# Load_Cell_Acquisition.net
KiCad netlist of a schematic drawn in Altium Designer
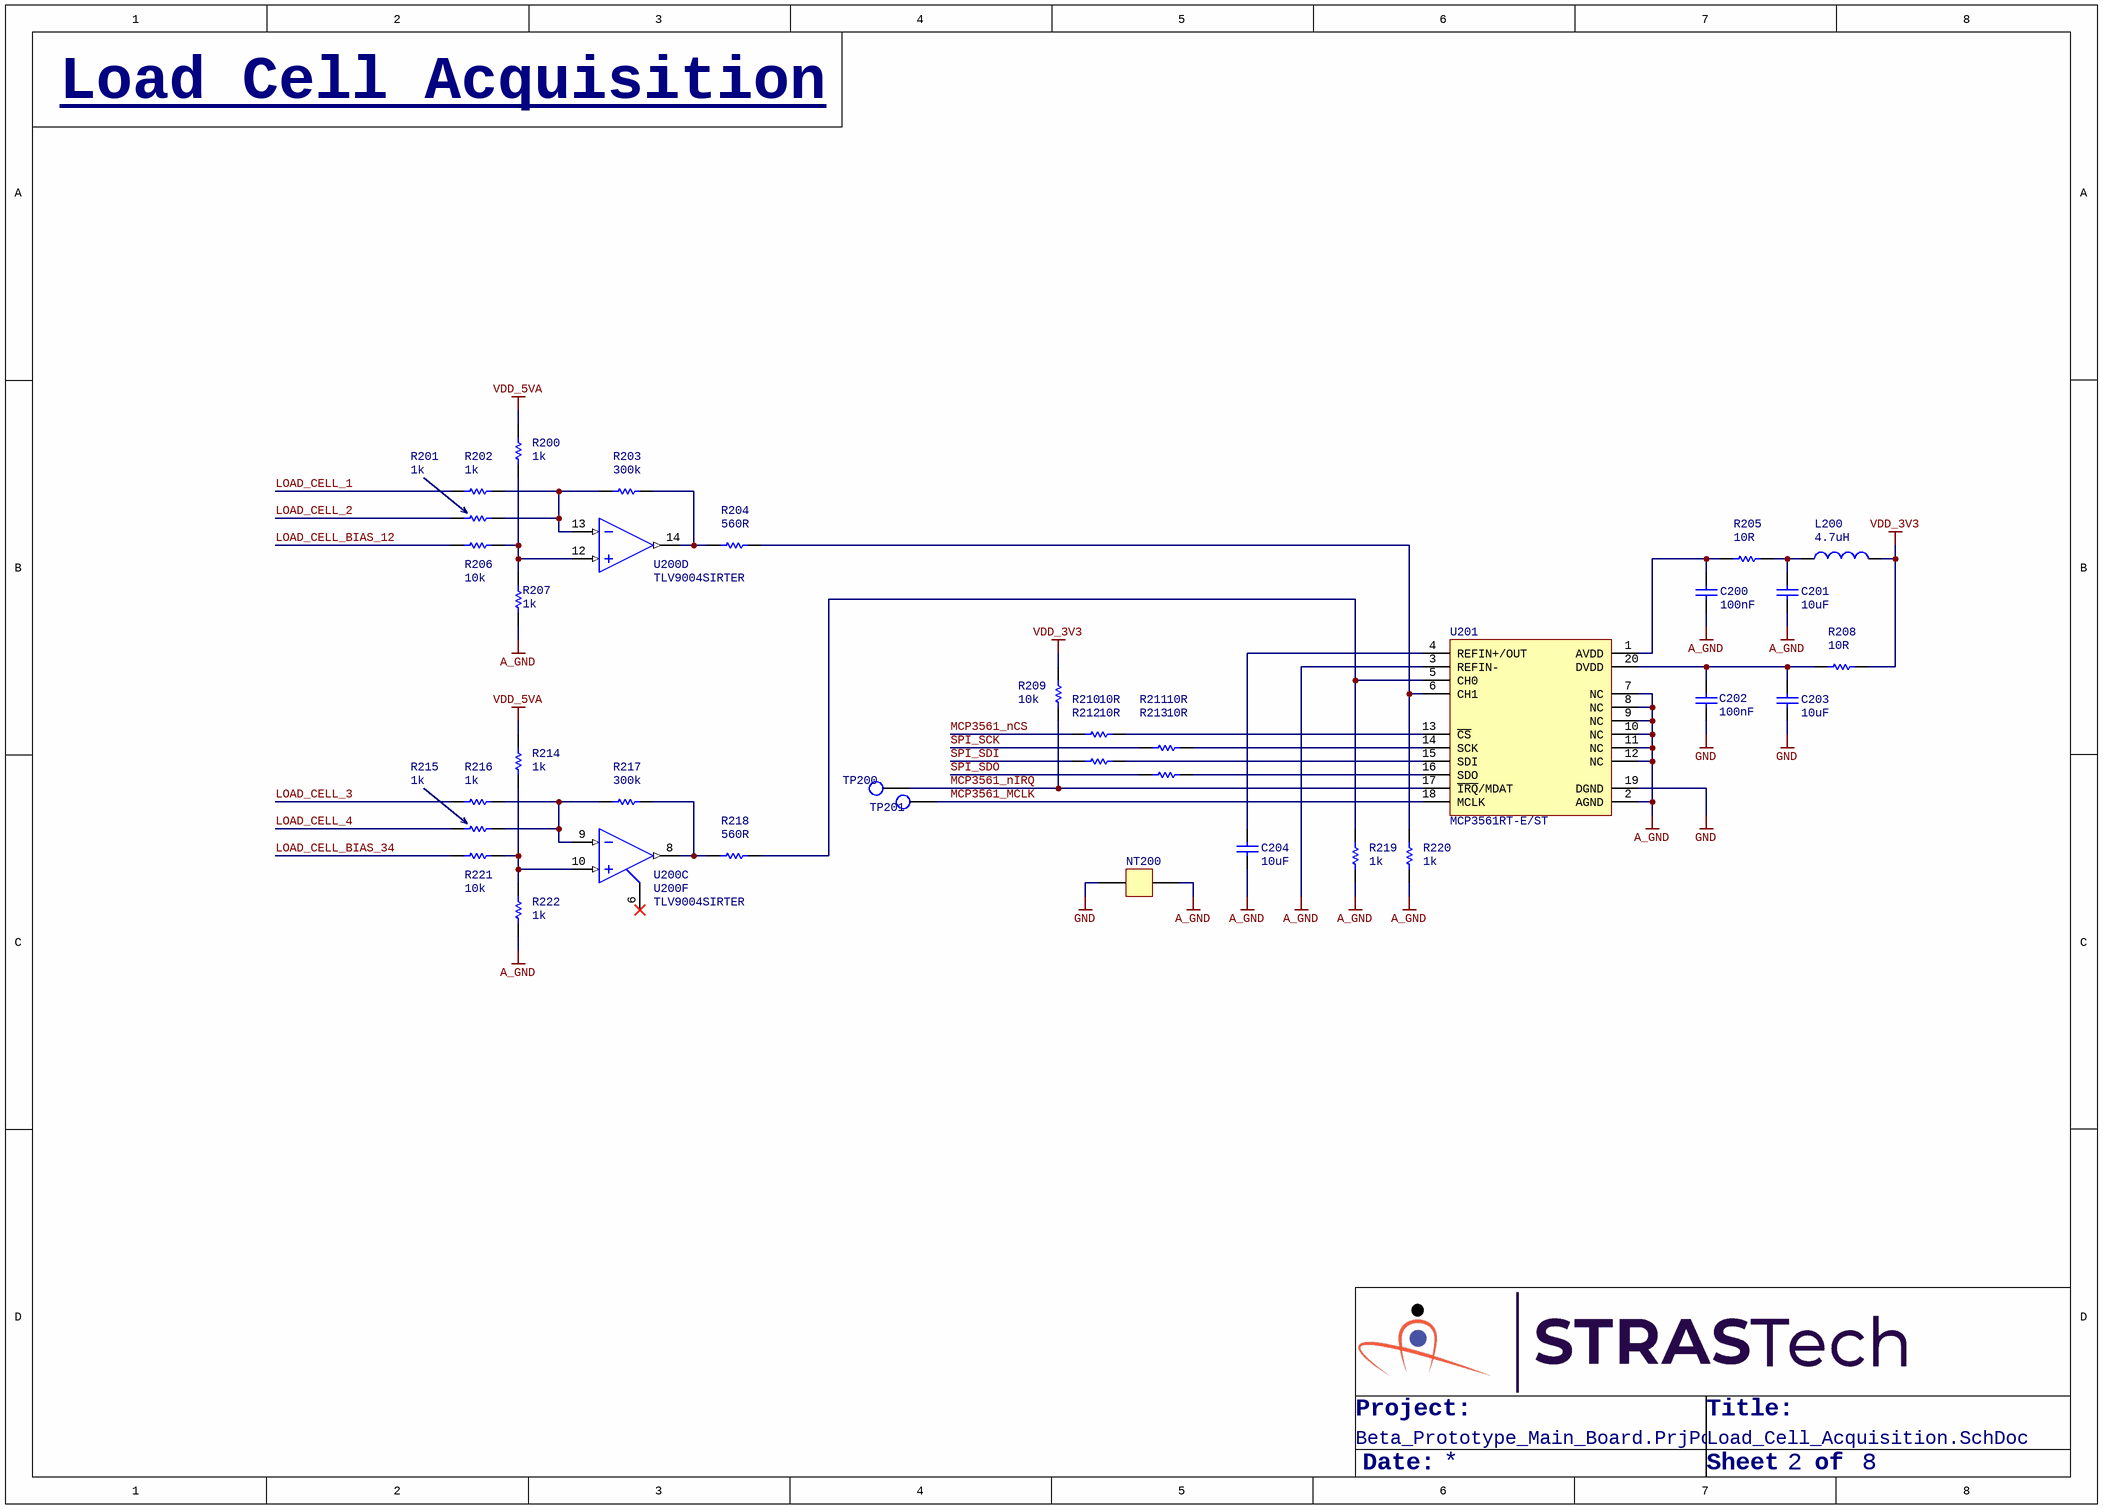
[diagram p0: Load_Cell_Acquisition.SchDoc]

(export (version "E")
  (design (tool "Eeschema 10.0.6"))
  (components
    (comp (ref "C200")
      (value "100nF")
      (footprint "Cap,SMD,0402")
      (description "0.1µF ±10% 25V Ceramic Capacitor X7R 0402 (1005 Metric)")
      (fields
        (field (name "VENDOR PART NUMBER") "490-14603-1-ND")
        (field (name "MANUFACTURER") "Murata Electronics")
        (field (name "CREATEDBY") "Judd Foster")
      )
      (libsource (lib "symbols") (part "CAP,Cer,100nF,25VDC,X7R,0402"))
    )
    (comp (ref "C201")
      (value "10uF")
      (footprint "Cap,SMD,0402")
      (description "10 µF ±20% 10V Ceramic Capacitor X5R 0402 (1005 Metric)")
      (fields
        (field (name "VENDOR PART NUMBER") "1276-1450-1-ND")
        (field (name "MANUFACTURER") "Samsung Electro-Mechanics")
        (field (name "CREATEDBY") "Judd Foster")
      )
      (libsource (lib "symbols") (part "CAP,Cer,10uF,10VDC,X5R,0402"))
    )
    (comp (ref "C202")
      (value "100nF")
      (footprint "Cap,SMD,0402")
      (description "0.1µF ±10% 25V Ceramic Capacitor X7R 0402 (1005 Metric)")
      (fields
        (field (name "VENDOR PART NUMBER") "490-14603-1-ND")
        (field (name "MANUFACTURER") "Murata Electronics")
        (field (name "CREATEDBY") "Judd Foster")
      )
      (libsource (lib "symbols") (part "CAP,Cer,100nF,25VDC,X7R,0402"))
    )
    (comp (ref "C203")
      (value "10uF")
      (footprint "Cap,SMD,0402")
      (description "10 µF ±20% 10V Ceramic Capacitor X5R 0402 (1005 Metric)")
      (fields
        (field (name "VENDOR PART NUMBER") "1276-1450-1-ND")
        (field (name "MANUFACTURER") "Samsung Electro-Mechanics")
        (field (name "CREATEDBY") "Judd Foster")
      )
      (libsource (lib "symbols") (part "CAP,Cer,10uF,10VDC,X5R,0402"))
    )
    (comp (ref "C204")
      (value "10uF")
      (footprint "Cap,SMD,0402")
      (description "10 µF ±20% 10V Ceramic Capacitor X5R 0402 (1005 Metric)")
      (fields
        (field (name "VENDOR PART NUMBER") "1276-1450-1-ND")
        (field (name "MANUFACTURER") "Samsung Electro-Mechanics")
        (field (name "CREATEDBY") "Judd Foster")
      )
      (libsource (lib "symbols") (part "CAP,Cer,10uF,10VDC,X5R,0402"))
    )
    (comp (ref "L200")
      (value "4.7uH")
      (footprint "IND,0805")
      (description "4.7 µH Shielded Multilayer Inductor 80 mA 300mOhm 0805 (2012 Metric)")
      (fields
        (field (name "VENDOR PART NUMBER") "445-3169-1-ND")
        (field (name "MANUFACTURER") "TDK Corporation")
        (field (name "CREATEDBY") "Judd Foster")
      )
      (libsource (lib "symbols") (part "IND,4.7uH,80mA,Multilayer,0805"))
    )
    (comp (ref "NT200")
      (value "Net Tie")
      (footprint "Net Tie,20x60mil")
      (fields (field (name "CREATEDBY") "Makan Mousavi"))
      (libsource (lib "symbols") (part "Net Tie"))
    )
    (comp (ref "R200")
      (value "1k")
      (footprint "RES,0402")
      (description "1 kOhms ±5% 0.063W, 1/16W Chip Resistor 0402 (1005 Metric) Automotive AEC-Q200 Thick Film")
      (fields
        (field (name "VENDOR PART NUMBER") "RMCF0402JT1K00CT-ND")
        (field (name "MANUFACTURER") "Stackpole Electronics Inc")
        (field (name "CREATEDBY") "Judd Foster")
      )
      (libsource (lib "symbols") (part "RES,1k,5%,0.063W,0402"))
    )
    (comp (ref "R201")
      (value "1k")
      (footprint "RES,0402")
      (description "1 kOhms ±5% 0.063W, 1/16W Chip Resistor 0402 (1005 Metric) Automotive AEC-Q200 Thick Film")
      (fields
        (field (name "VENDOR PART NUMBER") "RMCF0402JT1K00CT-ND")
        (field (name "MANUFACTURER") "Stackpole Electronics Inc")
        (field (name "CREATEDBY") "Judd Foster")
      )
      (libsource (lib "symbols") (part "RES,1k,5%,0.063W,0402"))
    )
    (comp (ref "R202")
      (value "1k")
      (footprint "RES,0402")
      (description "1 kOhms ±5% 0.063W, 1/16W Chip Resistor 0402 (1005 Metric) Automotive AEC-Q200 Thick Film")
      (fields
        (field (name "VENDOR PART NUMBER") "RMCF0402JT1K00CT-ND")
        (field (name "MANUFACTURER") "Stackpole Electronics Inc")
        (field (name "CREATEDBY") "Judd Foster")
      )
      (libsource (lib "symbols") (part "RES,1k,5%,0.063W,0402"))
    )
    (comp (ref "R203")
      (value "300k")
      (footprint "RES,0402")
      (description "300 kOhms ±1% 0.063W, 1/16W Chip Resistor 0402 (1005 Metric) Automotive AEC-Q200 Thick Film")
      (fields
        (field (name "MANUFACTURER") "Stackpole Electronics Inc")
        (field (name "MANUFACTURER PART NUMBER") "RMCF0402FT300K")
        (field (name "CREATEDBY") "Judd Foster")
      )
      (libsource (lib "symbols") (part "RES,300k,1%,0.063W,0402"))
    )
    (comp (ref "R204")
      (value "560R")
      (footprint "RES,0402")
      (fields
        (field (name "MANUFACTURER") "TE Connectivity Passive Product")
        (field (name "MANUFACTURER PART NUMBER") "CRGCQ0402F560R")
        (field (name "VENDOR PART NUMBER") "A129624CT-ND")
        (field (name "CREATEDBY") "Judd Foster")
      )
      (libsource (lib "symbols") (part "RES,560R,1%,0.063W,0402"))
    )
    (comp (ref "R205")
      (value "10R")
      (footprint "RES,0402")
      (description "10 Ohms ±1% 0.063W, 1/16W Chip Resistor 0402 (1005 Metric) Automotive AEC-Q200 Thick Film")
      (fields
        (field (name "MANUFACTURER") "Panasonic Electronic Components")
        (field (name "MANUFACTURER PART NUMBER") "ERJ-2RKF10R0X")
        (field (name "CREATEDBY") "Judd Foster")
      )
      (libsource (lib "symbols") (part "RES,10R,1%,0.063W,0402"))
    )
    (comp (ref "R206")
      (value "10k")
      (footprint "RES,0402")
      (description "10 kOhms ±5% 0.063W, 1/16W Chip Resistor 0402 (1005 Metric) Automotive AEC-Q200 Thick Film")
      (fields
        (field (name "VENDOR PART NUMBER") "RMCF0402JT10K0CT-ND")
        (field (name "MANUFACTURER") "Stackpole Electronics Inc")
        (field (name "CREATEDBY") "Judd Foster")
      )
      (libsource (lib "symbols") (part "RES,10k,5%,0.063W,0402"))
    )
    (comp (ref "R207")
      (value "1k")
      (footprint "RES,0402")
      (description "1 kOhms ±5% 0.063W, 1/16W Chip Resistor 0402 (1005 Metric) Automotive AEC-Q200 Thick Film")
      (fields
        (field (name "VENDOR PART NUMBER") "RMCF0402JT1K00CT-ND")
        (field (name "MANUFACTURER") "Stackpole Electronics Inc")
        (field (name "CREATEDBY") "Judd Foster")
      )
      (libsource (lib "symbols") (part "RES,1k,5%,0.063W,0402"))
    )
    (comp (ref "R208")
      (value "10R")
      (footprint "RES,0402")
      (description "10 Ohms ±1% 0.063W, 1/16W Chip Resistor 0402 (1005 Metric) Automotive AEC-Q200 Thick Film")
      (fields
        (field (name "MANUFACTURER") "Panasonic Electronic Components")
        (field (name "MANUFACTURER PART NUMBER") "ERJ-2RKF10R0X")
        (field (name "CREATEDBY") "Judd Foster")
      )
      (libsource (lib "symbols") (part "RES,10R,1%,0.063W,0402"))
    )
    (comp (ref "R209")
      (value "10k")
      (footprint "RES,0402")
      (description "10 kOhms ±5% 0.063W, 1/16W Chip Resistor 0402 (1005 Metric) Automotive AEC-Q200 Thick Film")
      (fields
        (field (name "VENDOR PART NUMBER") "RMCF0402JT10K0CT-ND")
        (field (name "MANUFACTURER") "Stackpole Electronics Inc")
        (field (name "CREATEDBY") "Judd Foster")
      )
      (libsource (lib "symbols") (part "RES,10k,5%,0.063W,0402"))
    )
    (comp (ref "R210")
      (value "10R")
      (footprint "RES,0402")
      (description "10 Ohms ±1% 0.063W, 1/16W Chip Resistor 0402 (1005 Metric) Automotive AEC-Q200 Thick Film")
      (fields
        (field (name "MANUFACTURER") "Panasonic Electronic Components")
        (field (name "MANUFACTURER PART NUMBER") "ERJ-2RKF10R0X")
        (field (name "CREATEDBY") "Judd Foster")
      )
      (libsource (lib "symbols") (part "RES,10R,1%,0.063W,0402"))
    )
    (comp (ref "R211")
      (value "10R")
      (footprint "RES,0402")
      (description "10 Ohms ±1% 0.063W, 1/16W Chip Resistor 0402 (1005 Metric) Automotive AEC-Q200 Thick Film")
      (fields
        (field (name "MANUFACTURER") "Panasonic Electronic Components")
        (field (name "MANUFACTURER PART NUMBER") "ERJ-2RKF10R0X")
        (field (name "CREATEDBY") "Judd Foster")
      )
      (libsource (lib "symbols") (part "RES,10R,1%,0.063W,0402"))
    )
    (comp (ref "R212")
      (value "10R")
      (footprint "RES,0402")
      (description "10 Ohms ±1% 0.063W, 1/16W Chip Resistor 0402 (1005 Metric) Automotive AEC-Q200 Thick Film")
      (fields
        (field (name "MANUFACTURER") "Panasonic Electronic Components")
        (field (name "MANUFACTURER PART NUMBER") "ERJ-2RKF10R0X")
        (field (name "CREATEDBY") "Judd Foster")
      )
      (libsource (lib "symbols") (part "RES,10R,1%,0.063W,0402"))
    )
    (comp (ref "R213")
      (value "10R")
      (footprint "RES,0402")
      (description "10 Ohms ±1% 0.063W, 1/16W Chip Resistor 0402 (1005 Metric) Automotive AEC-Q200 Thick Film")
      (fields
        (field (name "MANUFACTURER") "Panasonic Electronic Components")
        (field (name "MANUFACTURER PART NUMBER") "ERJ-2RKF10R0X")
        (field (name "CREATEDBY") "Judd Foster")
      )
      (libsource (lib "symbols") (part "RES,10R,1%,0.063W,0402"))
    )
    (comp (ref "R214")
      (value "1k")
      (footprint "RES,0402")
      (description "1 kOhms ±5% 0.063W, 1/16W Chip Resistor 0402 (1005 Metric) Automotive AEC-Q200 Thick Film")
      (fields
        (field (name "VENDOR PART NUMBER") "RMCF0402JT1K00CT-ND")
        (field (name "MANUFACTURER") "Stackpole Electronics Inc")
        (field (name "CREATEDBY") "Judd Foster")
      )
      (libsource (lib "symbols") (part "RES,1k,5%,0.063W,0402"))
    )
    (comp (ref "R215")
      (value "1k")
      (footprint "RES,0402")
      (description "1 kOhms ±5% 0.063W, 1/16W Chip Resistor 0402 (1005 Metric) Automotive AEC-Q200 Thick Film")
      (fields
        (field (name "VENDOR PART NUMBER") "RMCF0402JT1K00CT-ND")
        (field (name "MANUFACTURER") "Stackpole Electronics Inc")
        (field (name "CREATEDBY") "Judd Foster")
      )
      (libsource (lib "symbols") (part "RES,1k,5%,0.063W,0402"))
    )
    (comp (ref "R216")
      (value "1k")
      (footprint "RES,0402")
      (description "1 kOhms ±5% 0.063W, 1/16W Chip Resistor 0402 (1005 Metric) Automotive AEC-Q200 Thick Film")
      (fields
        (field (name "VENDOR PART NUMBER") "RMCF0402JT1K00CT-ND")
        (field (name "MANUFACTURER") "Stackpole Electronics Inc")
        (field (name "CREATEDBY") "Judd Foster")
      )
      (libsource (lib "symbols") (part "RES,1k,5%,0.063W,0402"))
    )
    (comp (ref "R217")
      (value "300k")
      (footprint "RES,0402")
      (description "300 kOhms ±1% 0.063W, 1/16W Chip Resistor 0402 (1005 Metric) Automotive AEC-Q200 Thick Film")
      (fields
        (field (name "MANUFACTURER") "Stackpole Electronics Inc")
        (field (name "MANUFACTURER PART NUMBER") "RMCF0402FT300K")
        (field (name "CREATEDBY") "Judd Foster")
      )
      (libsource (lib "symbols") (part "RES,300k,1%,0.063W,0402"))
    )
    (comp (ref "R218")
      (value "560R")
      (footprint "RES,0402")
      (fields
        (field (name "MANUFACTURER") "TE Connectivity Passive Product")
        (field (name "MANUFACTURER PART NUMBER") "CRGCQ0402F560R")
        (field (name "VENDOR PART NUMBER") "A129624CT-ND")
        (field (name "CREATEDBY") "Judd Foster")
      )
      (libsource (lib "symbols") (part "RES,560R,1%,0.063W,0402"))
    )
    (comp (ref "R219")
      (value "1k")
      (footprint "RES,0402")
      (description "1 kOhms ±5% 0.063W, 1/16W Chip Resistor 0402 (1005 Metric) Automotive AEC-Q200 Thick Film")
      (fields
        (field (name "VENDOR PART NUMBER") "RMCF0402JT1K00CT-ND")
        (field (name "MANUFACTURER") "Stackpole Electronics Inc")
        (field (name "CREATEDBY") "Judd Foster")
      )
      (libsource (lib "symbols") (part "RES,1k,5%,0.063W,0402"))
    )
    (comp (ref "R220")
      (value "1k")
      (footprint "RES,0402")
      (description "1 kOhms ±5% 0.063W, 1/16W Chip Resistor 0402 (1005 Metric) Automotive AEC-Q200 Thick Film")
      (fields
        (field (name "VENDOR PART NUMBER") "RMCF0402JT1K00CT-ND")
        (field (name "MANUFACTURER") "Stackpole Electronics Inc")
        (field (name "CREATEDBY") "Judd Foster")
      )
      (libsource (lib "symbols") (part "RES,1k,5%,0.063W,0402"))
    )
    (comp (ref "R221")
      (value "10k")
      (footprint "RES,0402")
      (description "10 kOhms ±5% 0.063W, 1/16W Chip Resistor 0402 (1005 Metric) Automotive AEC-Q200 Thick Film")
      (fields
        (field (name "VENDOR PART NUMBER") "RMCF0402JT10K0CT-ND")
        (field (name "MANUFACTURER") "Stackpole Electronics Inc")
        (field (name "CREATEDBY") "Judd Foster")
      )
      (libsource (lib "symbols") (part "RES,10k,5%,0.063W,0402"))
    )
    (comp (ref "R222")
      (value "1k")
      (footprint "RES,0402")
      (description "1 kOhms ±5% 0.063W, 1/16W Chip Resistor 0402 (1005 Metric) Automotive AEC-Q200 Thick Film")
      (fields
        (field (name "VENDOR PART NUMBER") "RMCF0402JT1K00CT-ND")
        (field (name "MANUFACTURER") "Stackpole Electronics Inc")
        (field (name "CREATEDBY") "Judd Foster")
      )
      (libsource (lib "symbols") (part "RES,1k,5%,0.063W,0402"))
    )
    (comp (ref "TP200")
      (value "TESTPOINT")
      (footprint "testpoint,smd,round,1mm")
      (description "PCB Testpoint")
      (fields (field (name "CREATEDBY") "Judd Foster"))
      (libsource (lib "symbols") (part "TESTPOINT"))
    )
    (comp (ref "TP201")
      (value "TESTPOINT")
      (footprint "testpoint,smd,round,1mm")
      (description "PCB Testpoint")
      (fields (field (name "CREATEDBY") "Judd Foster"))
      (libsource (lib "symbols") (part "TESTPOINT"))
    )
    (comp (ref "U200")
      (value "TLV9004SIRTER")
      (footprint "IC,QFN-16,3x3")
      (description "General Purpose Amplifier 4 Circuit Rail-to-Rail 16-WQFN (3x3)")
      (fields
        (field (name "MANUFACTURER") "Texas Instruments")
        (field (name "VENDOR PART NUMBER") "296-51829-1-ND")
        (field (name "CREATEDBY") "Judd Foster")
      )
      (libsource (lib "symbols") (part "TLV9004SIRTER"))
    )
    (comp (ref "U201")
      (value "MCP3561RT-E/ST")
      (footprint "IC,TSSOP-20,W4.4")
      (description "24 Bit Analog to Digital Converter 1 Input 1 Sigma-Delta 20-TSSOP")
      (fields
        (field (name "VENDOR PART NUMBER") "150-MCP3561RT-E/STCT-ND")
        (field (name "MANUFACTURER") "Microchip Technology")
        (field (name "CREATEDBY") "Judd Foster")
      )
      (libsource (lib "symbols") (part "MCP3561RT-E/ST"))
    )
  )
  (nets
    (net (code "1") (name "/LOAD_CELL_1") (class "Default")
      (node (ref "R202") (pin "2") (pinfunction "2_2") (pintype "passive"))
    )
    (net (code "2") (name "/LOAD_CELL_2") (class "Default")
      (node (ref "R201") (pin "2") (pinfunction "2_2") (pintype "passive"))
    )
    (net (code "3") (name "/LOAD_CELL_3") (class "Default")
      (node (ref "R216") (pin "2") (pinfunction "2_2") (pintype "passive"))
    )
    (net (code "4") (name "/LOAD_CELL_4") (class "Default")
      (node (ref "R215") (pin "2") (pinfunction "2_2") (pintype "passive"))
    )
    (net (code "5") (name "/LOAD_CELL_BIAS_12") (class "Default")
      (node (ref "R206") (pin "1") (pinfunction "1_1") (pintype "passive"))
    )
    (net (code "6") (name "/LOAD_CELL_BIAS_34") (class "Default")
      (node (ref "R221") (pin "1") (pinfunction "1_1") (pintype "passive"))
    )
    (net (code "7") (name "/MCP3561_MCLK") (class "Default")
      (node (ref "TP201") (pin "1") (pinfunction "TP_1") (pintype "passive"))
      (node (ref "U201") (pin "18") (pinfunction "MCLK_18") (pintype "passive"))
    )
    (net (code "8") (name "/MCP3561_nCS") (class "Default")
      (node (ref "R210") (pin "1") (pinfunction "1_1") (pintype "passive"))
    )
    (net (code "9") (name "/MCP3561_nIRQ") (class "Default")
      (node (ref "R209") (pin "1") (pinfunction "1_1") (pintype "passive"))
      (node (ref "TP200") (pin "1") (pinfunction "TP_1") (pintype "passive"))
      (node (ref "U201") (pin "17") (pinfunction "~{IRQ}/MDAT_17") (pintype "passive"))
    )
    (net (code "10") (name "/SPI_SCK") (class "Default")
      (node (ref "R211") (pin "1") (pinfunction "1_1") (pintype "passive"))
    )
    (net (code "11") (name "/SPI_SDI") (class "Default")
      (node (ref "R212") (pin "1") (pinfunction "1_1") (pintype "passive"))
    )
    (net (code "12") (name "/SPI_SDO") (class "Default")
      (node (ref "R213") (pin "1") (pinfunction "1_1") (pintype "passive"))
    )
    (net (code "13") (name "A_GND") (class "Default")
      (node (ref "C200") (pin "1") (pinfunction "1_1") (pintype "passive"))
      (node (ref "C201") (pin "2") (pinfunction "2_2") (pintype "passive"))
      (node (ref "C204") (pin "1") (pinfunction "1_1") (pintype "passive"))
      (node (ref "NT200") (pin "2") (pinfunction "2_2") (pintype "passive"))
      (node (ref "R207") (pin "1") (pinfunction "1_1") (pintype "passive"))
      (node (ref "R219") (pin "2") (pinfunction "2_2") (pintype "passive"))
      (node (ref "R220") (pin "2") (pinfunction "2_2") (pintype "passive"))
      (node (ref "R222") (pin "1") (pinfunction "1_1") (pintype "passive"))
      (node (ref "U201") (pin "10") (pinfunction "NC_10") (pintype "passive"))
      (node (ref "U201") (pin "11") (pinfunction "NC_11") (pintype "passive"))
      (node (ref "U201") (pin "12") (pinfunction "NC_12") (pintype "passive"))
      (node (ref "U201") (pin "2") (pinfunction "AGND_2") (pintype "passive"))
      (node (ref "U201") (pin "3") (pinfunction "REFIN-_3") (pintype "passive"))
      (node (ref "U201") (pin "7") (pinfunction "NC_7") (pintype "passive"))
      (node (ref "U201") (pin "8") (pinfunction "NC_8") (pintype "passive"))
      (node (ref "U201") (pin "9") (pinfunction "NC_9") (pintype "passive"))
    )
    (net (code "14") (name "GND") (class "Default")
      (node (ref "C202") (pin "1") (pinfunction "1_1") (pintype "passive"))
      (node (ref "C203") (pin "2") (pinfunction "2_2") (pintype "passive"))
      (node (ref "NT200") (pin "1") (pinfunction "1_1") (pintype "passive"))
      (node (ref "U201") (pin "19") (pinfunction "DGND_19") (pintype "passive"))
    )
    (net (code "15") (name "Net-(C201-Pad1)") (class "Default")
      (node (ref "C201") (pin "1") (pinfunction "1_1") (pintype "passive"))
      (node (ref "L200") (pin "1") (pinfunction "1_1") (pintype "passive"))
      (node (ref "R205") (pin "2") (pinfunction "2_2") (pintype "passive"))
    )
    (net (code "16") (name "Net-(U200C-IN3+)") (class "Default")
      (node (ref "R214") (pin "1") (pinfunction "1_1") (pintype "passive"))
      (node (ref "R221") (pin "2") (pinfunction "2_2") (pintype "passive"))
      (node (ref "R222") (pin "2") (pinfunction "2_2") (pintype "passive"))
      (node (ref "U200") (pin "10") (pinfunction "IN3+_10") (pintype "input"))
    )
    (net (code "17") (name "Net-(U200C-IN3-)") (class "Default")
      (node (ref "R215") (pin "1") (pinfunction "1_1") (pintype "passive"))
      (node (ref "R216") (pin "1") (pinfunction "1_1") (pintype "passive"))
      (node (ref "R217") (pin "2") (pinfunction "2_2") (pintype "passive"))
      (node (ref "U200") (pin "9") (pinfunction "IN3-_9") (pintype "input"))
    )
    (net (code "18") (name "Net-(U200C-OUT3)") (class "Default")
      (node (ref "R217") (pin "1") (pinfunction "1_1") (pintype "passive"))
      (node (ref "R218") (pin "2") (pinfunction "2_2") (pintype "passive"))
      (node (ref "U200") (pin "8") (pinfunction "OUT3_8") (pintype "output"))
    )
    (net (code "19") (name "Net-(U200D-IN4+)") (class "Default")
      (node (ref "R200") (pin "1") (pinfunction "1_1") (pintype "passive"))
      (node (ref "R206") (pin "2") (pinfunction "2_2") (pintype "passive"))
      (node (ref "R207") (pin "2") (pinfunction "2_2") (pintype "passive"))
      (node (ref "U200") (pin "12") (pinfunction "IN4+_12") (pintype "input"))
    )
    (net (code "20") (name "Net-(U200D-IN4-)") (class "Default")
      (node (ref "R201") (pin "1") (pinfunction "1_1") (pintype "passive"))
      (node (ref "R202") (pin "1") (pinfunction "1_1") (pintype "passive"))
      (node (ref "R203") (pin "2") (pinfunction "2_2") (pintype "passive"))
      (node (ref "U200") (pin "13") (pinfunction "IN4-_13") (pintype "input"))
    )
    (net (code "21") (name "Net-(U200D-OUT4)") (class "Default")
      (node (ref "R203") (pin "1") (pinfunction "1_1") (pintype "passive"))
      (node (ref "R204") (pin "2") (pinfunction "2_2") (pintype "passive"))
      (node (ref "U200") (pin "14") (pinfunction "OUT4_14") (pintype "output"))
    )
    (net (code "22") (name "Net-(U201-AVDD)") (class "Default")
      (node (ref "C200") (pin "2") (pinfunction "2_2") (pintype "passive"))
      (node (ref "R205") (pin "1") (pinfunction "1_1") (pintype "passive"))
      (node (ref "U201") (pin "1") (pinfunction "AVDD_1") (pintype "passive"))
    )
    (net (code "23") (name "Net-(U201-CH0)") (class "Default")
      (node (ref "R218") (pin "1") (pinfunction "1_1") (pintype "passive"))
      (node (ref "R219") (pin "1") (pinfunction "1_1") (pintype "passive"))
      (node (ref "U201") (pin "5") (pinfunction "CH0_5") (pintype "passive"))
    )
    (net (code "24") (name "Net-(U201-CH1)") (class "Default")
      (node (ref "R204") (pin "1") (pinfunction "1_1") (pintype "passive"))
      (node (ref "R220") (pin "1") (pinfunction "1_1") (pintype "passive"))
      (node (ref "U201") (pin "6") (pinfunction "CH1_6") (pintype "passive"))
    )
    (net (code "25") (name "Net-(U201-DVDD)") (class "Default")
      (node (ref "C202") (pin "2") (pinfunction "2_2") (pintype "passive"))
      (node (ref "C203") (pin "1") (pinfunction "1_1") (pintype "passive"))
      (node (ref "R208") (pin "1") (pinfunction "1_1") (pintype "passive"))
      (node (ref "U201") (pin "20") (pinfunction "DVDD_20") (pintype "passive"))
    )
    (net (code "26") (name "Net-(U201-REFIN+{slash}OUT)") (class "Default")
      (node (ref "C204") (pin "2") (pinfunction "2_2") (pintype "passive"))
      (node (ref "U201") (pin "4") (pinfunction "REFIN+/OUT_4") (pintype "passive"))
    )
    (net (code "27") (name "Net-(U201-SCK)") (class "Default")
      (node (ref "R211") (pin "2") (pinfunction "2_2") (pintype "passive"))
      (node (ref "U201") (pin "14") (pinfunction "SCK_14") (pintype "passive"))
    )
    (net (code "28") (name "Net-(U201-SDI)") (class "Default")
      (node (ref "R212") (pin "2") (pinfunction "2_2") (pintype "passive"))
      (node (ref "U201") (pin "15") (pinfunction "SDI_15") (pintype "passive"))
    )
    (net (code "29") (name "Net-(U201-SDO)") (class "Default")
      (node (ref "R213") (pin "2") (pinfunction "2_2") (pintype "passive"))
      (node (ref "U201") (pin "16") (pinfunction "SDO_16") (pintype "passive"))
    )
    (net (code "30") (name "Net-(U201-~{CS})") (class "Default")
      (node (ref "R210") (pin "2") (pinfunction "2_2") (pintype "passive"))
      (node (ref "U201") (pin "13") (pinfunction "~{CS}_13") (pintype "passive"))
    )
    (net (code "31") (name "VDD_3V3") (class "Default")
      (node (ref "L200") (pin "2") (pinfunction "2_2") (pintype "passive"))
      (node (ref "R208") (pin "2") (pinfunction "2_2") (pintype "passive"))
      (node (ref "R209") (pin "2") (pinfunction "2_2") (pintype "passive"))
    )
    (net (code "32") (name "VDD_5VA") (class "Default")
      (node (ref "R200") (pin "2") (pinfunction "2_2") (pintype "passive"))
      (node (ref "R214") (pin "2") (pinfunction "2_2") (pintype "passive"))
    )
    (net (code "33") (name "unconnected-(U200F-~{SHDN}12-Pad6)") (class "Default")
      (node (ref "U200") (pin "6") (pinfunction "~{SHDN}12_6") (pintype "power_in+no_connect"))
    )
  )
)
